# ESCHeaders.net
KiCad netlist of a schematic drawn in Altium Designer
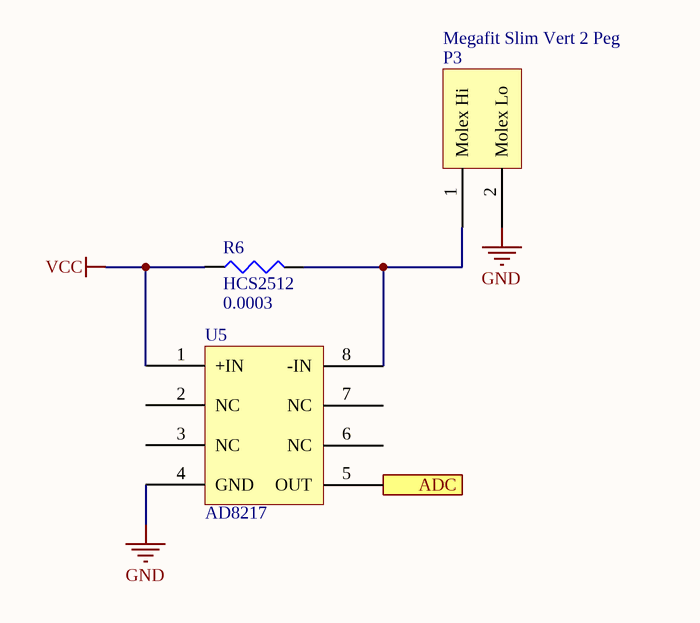
[diagram p0: ESCHeaders.SchDoc]

(export (version "E")
  (design (tool "Eeschema 10.0.6"))
  (components
    (comp (ref "P3")
      (value "Megafit Slim Vert 2 Peg")
      (footprint "Molex_DT:76829-0102")
      (fields (field (name "MFGR_PART_NUM") "76829-0102"))
      (libsource (lib "Molex_DT") (part "Megafit Slim Vert 2 Peg"))
    )
    (comp (ref "R6")
      (value "HCS2512")
      (footprint "HCS2512FTL300CT-ND_DT")
      (description "Resistor")
      (fields
        (field (name "ALTIUM_VALUE") "0.0003")
        (field (name "MFGR_PART_NUM") "HCS2512FTL300")
        (field (name "PUBLISHER") "Altium Limited")
      )
      (libsource (lib "Miscellaneous Devices") (part "Res3"))
    )
    (comp (ref "U5")
      (value "AD8217")
      (footprint "AD8217_DT:AD8217_DT")
      (fields (field (name "MFGR_PART_NUM") "AD8217BRMZ-R7"))
      (libsource (lib "AD8217_DT") (part "AD8217"))
    )
  )
  (nets
    (net (code "1") (name "/ADC") (class "Default")
      (node (ref "U5") (pin "5") (pinfunction "OUT_5") (pintype "passive"))
    )
    (net (code "2") (name "GND") (class "Default")
      (node (ref "P3") (pin "2") (pinfunction "Molex_Lo_2") (pintype "passive"))
      (node (ref "U5") (pin "4") (pinfunction "GND_4") (pintype "passive"))
    )
    (net (code "3") (name "Net-(P3-Molex_Hi)") (class "Default")
      (node (ref "P3") (pin "1") (pinfunction "Molex_Hi_1") (pintype "passive"))
      (node (ref "R6") (pin "2") (pinfunction "2_2") (pintype "passive"))
      (node (ref "U5") (pin "8") (pinfunction "-IN_8") (pintype "passive"))
    )
    (net (code "4") (name "VCC") (class "Default")
      (node (ref "R6") (pin "1") (pinfunction "1_1") (pintype "passive"))
      (node (ref "U5") (pin "1") (pinfunction "+IN_1") (pintype "passive"))
    )
    (net (code "5") (name "unconnected-(U5-NC-Pad2)") (class "Default")
      (node (ref "U5") (pin "2") (pinfunction "NC_2") (pintype "passive"))
    )
    (net (code "6") (name "unconnected-(U5-NC-Pad3)") (class "Default")
      (node (ref "U5") (pin "3") (pinfunction "NC_3") (pintype "passive"))
    )
    (net (code "7") (name "unconnected-(U5-NC-Pad6)") (class "Default")
      (node (ref "U5") (pin "6") (pinfunction "NC_6") (pintype "passive"))
    )
    (net (code "8") (name "unconnected-(U5-NC-Pad7)") (class "Default")
      (node (ref "U5") (pin "7") (pinfunction "NC_7") (pintype "passive"))
    )
  )
)
